# USB_debug_schematic.net
KiCad netlist of a schematic drawn in Altium Designer
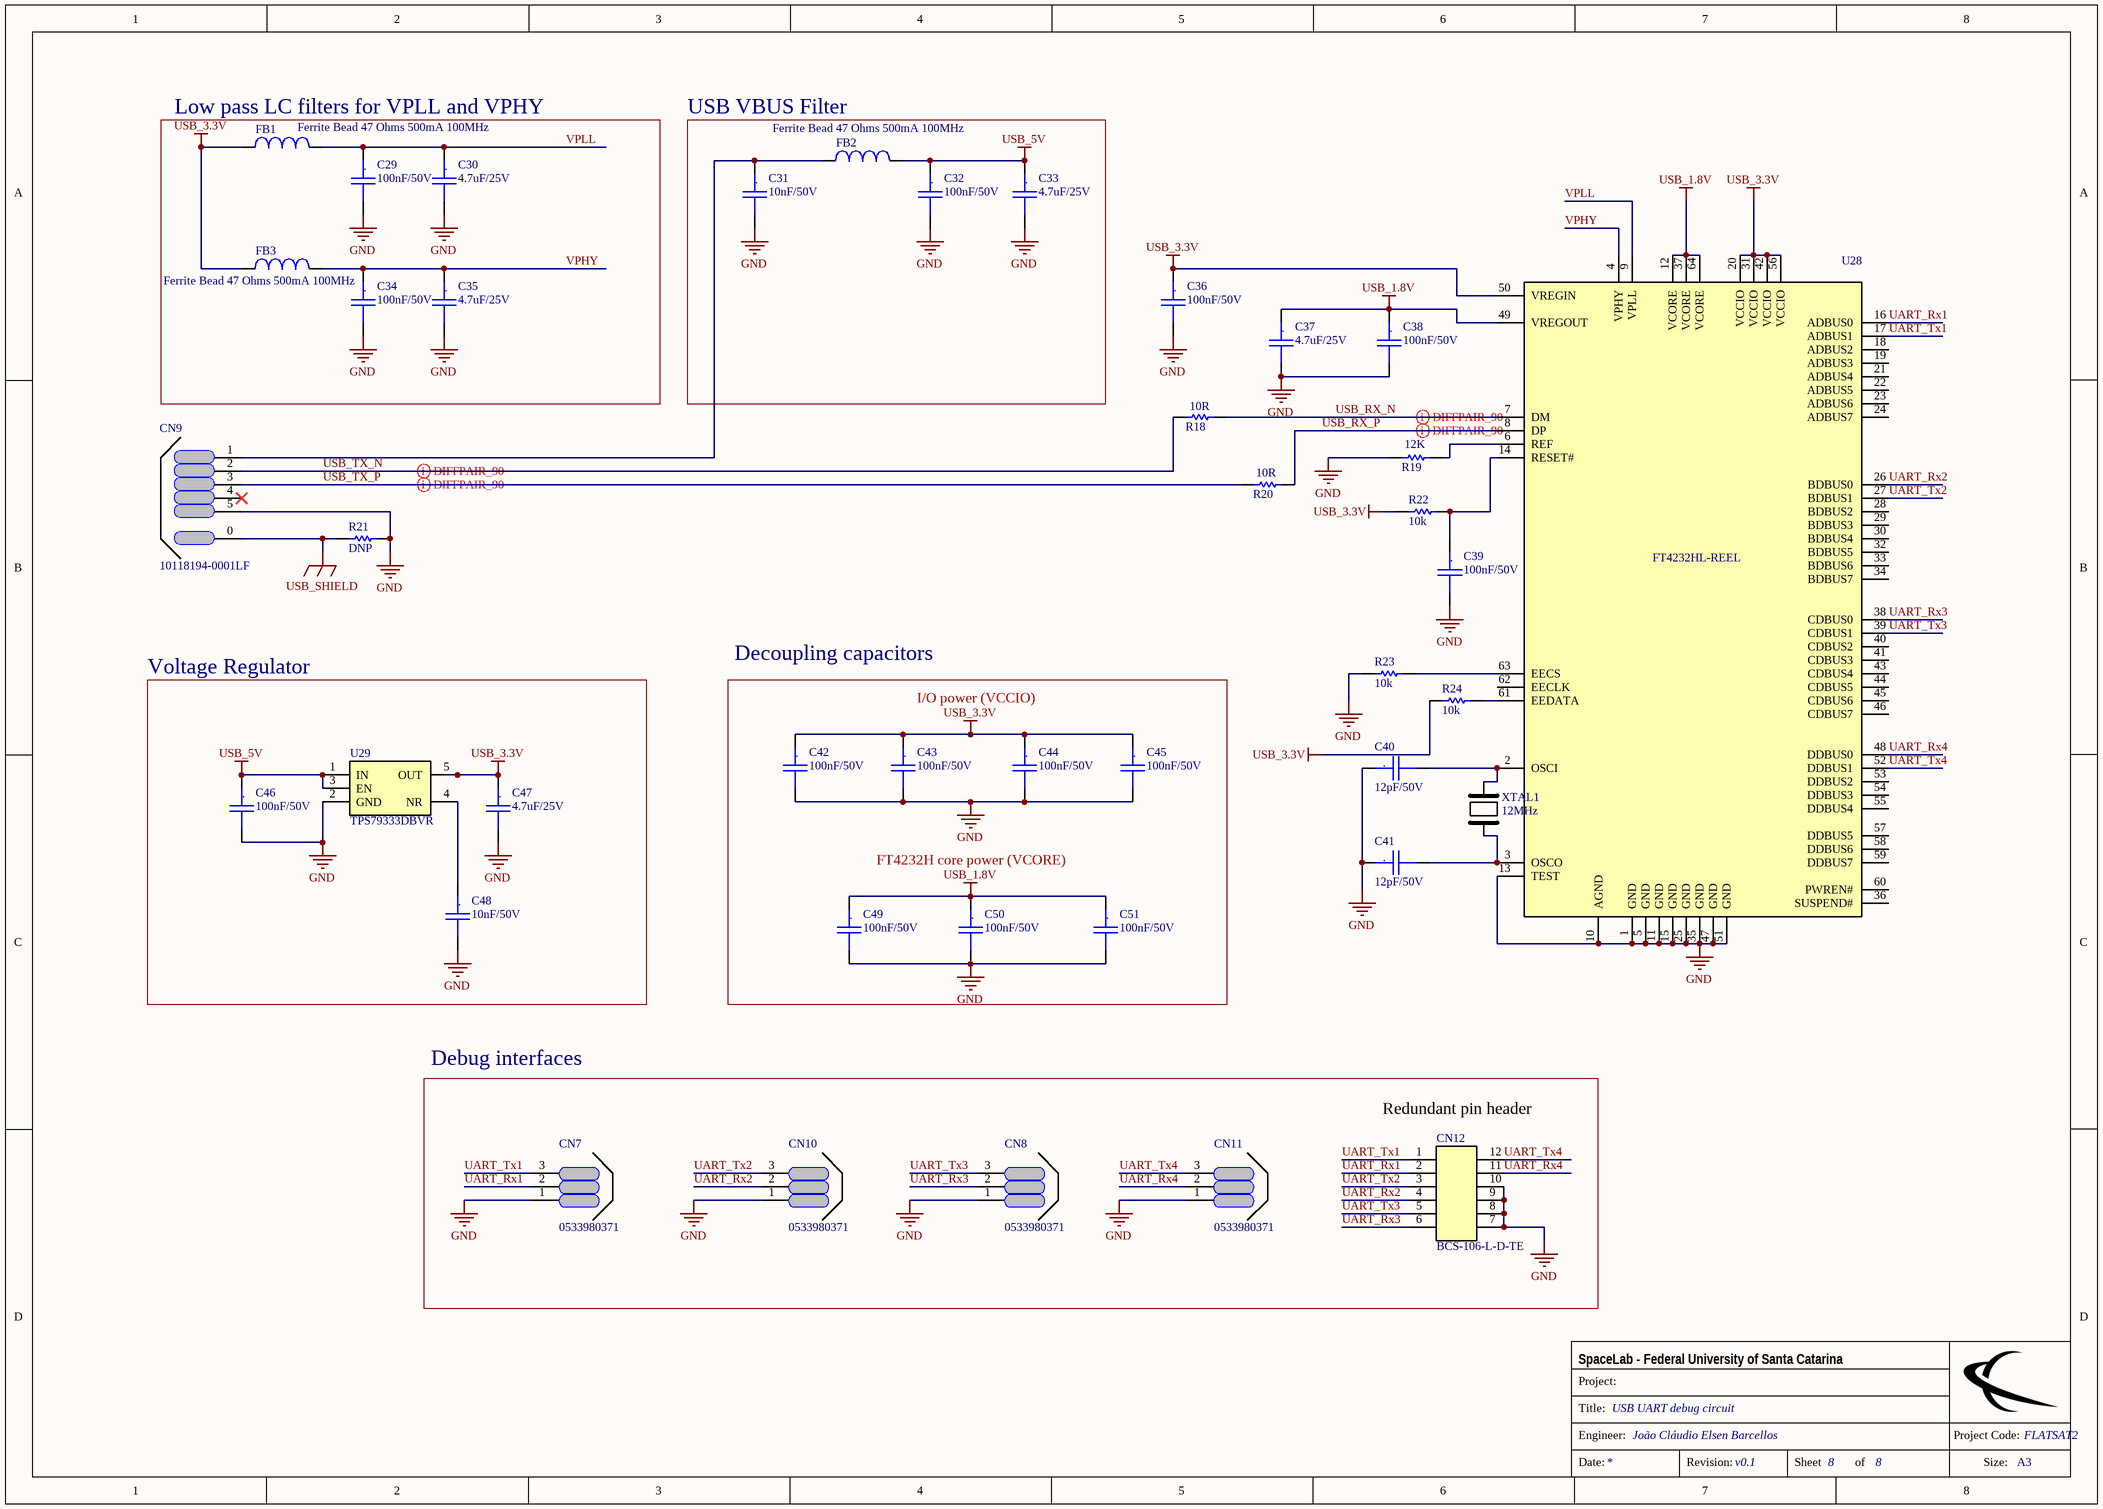
[diagram p0: USB_debug_schematic.SchDoc]

(export (version "E")
  (design (tool "Eeschema 10.0.6"))
  (components
    (comp (ref "C29")
      (value "100nF/50V")
      (footprint "CC0603")
      (description "CAP CER 100nF 50V 10% X7R 0603")
      (fields (field (name "MANUFACTURER PART NUMBER") "C0603C104K5RAC3121"))
      (libsource (lib "flatsat_platform_2") (part "Cap_Cer_X7R_100nF_50V_0603"))
    )
    (comp (ref "C30")
      (value "4.7uF/25V")
      (footprint "CC0805")
      (description "CAP CER 4.7uF 25V 10% X7R 0805")
      (fields (field (name "MANUFACTURER PART NUMBER") "C0805C475K3RACAUTO"))
      (libsource (lib "flatsat_platform_2") (part "Cap_Cer_X7R_4.7uF_25V_0805"))
    )
    (comp (ref "C31")
      (value "10nF/50V")
      (footprint "CC0805")
      (description "CAP CER 0.01uF 50V 10% X7R 0805")
      (fields (field (name "MANUFACTURER PART NUMBER") "08055C103KAT4A"))
      (libsource (lib "flatsat_platform_2") (part "Cap_Cer_X7R_10nF_50V_0805"))
    )
    (comp (ref "C32")
      (value "100nF/50V")
      (footprint "CC0603")
      (description "CAP CER 100nF 50V 10% X7R 0603")
      (fields (field (name "MANUFACTURER PART NUMBER") "C0603C104K5RAC3121"))
      (libsource (lib "flatsat_platform_2") (part "Cap_Cer_X7R_100nF_50V_0603"))
    )
    (comp (ref "C33")
      (value "4.7uF/25V")
      (footprint "CC0805")
      (description "CAP CER 4.7uF 25V 10% X7R 0805")
      (fields (field (name "MANUFACTURER PART NUMBER") "C0805C475K3RACAUTO"))
      (libsource (lib "flatsat_platform_2") (part "Cap_Cer_X7R_4.7uF_25V_0805"))
    )
    (comp (ref "C34")
      (value "100nF/50V")
      (footprint "CC0603")
      (description "CAP CER 100nF 50V 10% X7R 0603")
      (fields (field (name "MANUFACTURER PART NUMBER") "C0603C104K5RAC3121"))
      (libsource (lib "flatsat_platform_2") (part "Cap_Cer_X7R_100nF_50V_0603"))
    )
    (comp (ref "C35")
      (value "4.7uF/25V")
      (footprint "CC0805")
      (description "CAP CER 4.7uF 25V 10% X7R 0805")
      (fields (field (name "MANUFACTURER PART NUMBER") "C0805C475K3RACAUTO"))
      (libsource (lib "flatsat_platform_2") (part "Cap_Cer_X7R_4.7uF_25V_0805"))
    )
    (comp (ref "C36")
      (value "100nF/50V")
      (footprint "CC0603")
      (description "CAP CER 100nF 50V 10% X7R 0603")
      (fields (field (name "MANUFACTURER PART NUMBER") "C0603C104K5RAC3121"))
      (libsource (lib "flatsat_platform_2") (part "Cap_Cer_X7R_100nF_50V_0603"))
    )
    (comp (ref "C37")
      (value "4.7uF/25V")
      (footprint "CC0805")
      (description "CAP CER 4.7uF 25V 10% X7R 0805")
      (fields (field (name "MANUFACTURER PART NUMBER") "C0805C475K3RACAUTO"))
      (libsource (lib "flatsat_platform_2") (part "Cap_Cer_X7R_4.7uF_25V_0805"))
    )
    (comp (ref "C38")
      (value "100nF/50V")
      (footprint "CC0603")
      (description "CAP CER 100nF 50V 10% X7R 0603")
      (fields (field (name "MANUFACTURER PART NUMBER") "C0603C104K5RAC3121"))
      (libsource (lib "flatsat_platform_2") (part "Cap_Cer_X7R_100nF_50V_0603"))
    )
    (comp (ref "C39")
      (value "100nF/50V")
      (footprint "CC0603")
      (description "CAP CER 100nF 50V 10% X7R 0603")
      (fields (field (name "MANUFACTURER PART NUMBER") "C0603C104K5RAC3121"))
      (libsource (lib "flatsat_platform_2") (part "Cap_Cer_X7R_100nF_50V_0603"))
    )
    (comp (ref "C40")
      (value "12pF/50V")
      (footprint "CC0805")
      (description "CAP CER 12pF 50V 1% C0G/NP0 0805")
      (fields (field (name "MANUFACTURER PART NUMBER") "CL21C120FBANNNC"))
      (libsource (lib "flatsat_platform_2") (part "Cap_Cer_X7R_12pF_50V_0805"))
    )
    (comp (ref "C41")
      (value "12pF/50V")
      (footprint "CC0805")
      (description "CAP CER 12pF 50V 1% C0G/NP0 0805")
      (fields (field (name "MANUFACTURER PART NUMBER") "CL21C120FBANNNC"))
      (libsource (lib "flatsat_platform_2") (part "Cap_Cer_X7R_12pF_50V_0805"))
    )
    (comp (ref "C42")
      (value "100nF/50V")
      (footprint "CC0603")
      (description "CAP CER 100nF 50V 10% X7R 0603")
      (fields (field (name "MANUFACTURER PART NUMBER") "C0603C104K5RAC3121"))
      (libsource (lib "flatsat_platform_2") (part "Cap_Cer_X7R_100nF_50V_0603"))
    )
    (comp (ref "C43")
      (value "100nF/50V")
      (footprint "CC0603")
      (description "CAP CER 100nF 50V 10% X7R 0603")
      (fields (field (name "MANUFACTURER PART NUMBER") "C0603C104K5RAC3121"))
      (libsource (lib "flatsat_platform_2") (part "Cap_Cer_X7R_100nF_50V_0603"))
    )
    (comp (ref "C44")
      (value "100nF/50V")
      (footprint "CC0603")
      (description "CAP CER 100nF 50V 10% X7R 0603")
      (fields (field (name "MANUFACTURER PART NUMBER") "C0603C104K5RAC3121"))
      (libsource (lib "flatsat_platform_2") (part "Cap_Cer_X7R_100nF_50V_0603"))
    )
    (comp (ref "C45")
      (value "100nF/50V")
      (footprint "CC0603")
      (description "CAP CER 100nF 50V 10% X7R 0603")
      (fields (field (name "MANUFACTURER PART NUMBER") "C0603C104K5RAC3121"))
      (libsource (lib "flatsat_platform_2") (part "Cap_Cer_X7R_100nF_50V_0603"))
    )
    (comp (ref "C46")
      (value "100nF/50V")
      (footprint "CC0603")
      (description "CAP CER 100nF 50V 10% X7R 0603")
      (fields (field (name "MANUFACTURER PART NUMBER") "C0603C104K5RAC3121"))
      (libsource (lib "flatsat_platform_2") (part "Cap_Cer_X7R_100nF_50V_0603"))
    )
    (comp (ref "C47")
      (value "4.7uF/25V")
      (footprint "CC0805")
      (description "CAP CER 4.7uF 25V 10% X7R 0805")
      (fields (field (name "MANUFACTURER PART NUMBER") "C0805C475K3RACAUTO"))
      (libsource (lib "flatsat_platform_2") (part "Cap_Cer_X7R_4.7uF_25V_0805"))
    )
    (comp (ref "C48")
      (value "10nF/50V")
      (footprint "CC0805")
      (description "CAP CER 0.01uF 50V 10% X7R 0805")
      (fields (field (name "MANUFACTURER PART NUMBER") "08055C103KAT4A"))
      (libsource (lib "flatsat_platform_2") (part "Cap_Cer_X7R_10nF_50V_0805"))
    )
    (comp (ref "C49")
      (value "100nF/50V")
      (footprint "CC0603")
      (description "CAP CER 100nF 50V 10% X7R 0603")
      (fields (field (name "MANUFACTURER PART NUMBER") "C0603C104K5RAC3121"))
      (libsource (lib "flatsat_platform_2") (part "Cap_Cer_X7R_100nF_50V_0603"))
    )
    (comp (ref "C50")
      (value "100nF/50V")
      (footprint "CC0603")
      (description "CAP CER 100nF 50V 10% X7R 0603")
      (fields (field (name "MANUFACTURER PART NUMBER") "C0603C104K5RAC3121"))
      (libsource (lib "flatsat_platform_2") (part "Cap_Cer_X7R_100nF_50V_0603"))
    )
    (comp (ref "C51")
      (value "100nF/50V")
      (footprint "CC0603")
      (description "CAP CER 100nF 50V 10% X7R 0603")
      (fields (field (name "MANUFACTURER PART NUMBER") "C0603C104K5RAC3121"))
      (libsource (lib "flatsat_platform_2") (part "Cap_Cer_X7R_100nF_50V_0603"))
    )
    (comp (ref "CN7")
      (value "0533980371")
      (footprint "PICO BLADE 0533980371")
      (description "CONN HEADER SMD 3POS 1.25MM")
      (fields (field (name "MANUFACTURER") "Molex") (field (name "MANUFACTURER PART NUMBER") "53398-0371"))
      (libsource (lib "flatsat_platform_2") (part "0533980371"))
    )
    (comp (ref "CN8")
      (value "0533980371")
      (footprint "PICO BLADE 0533980371")
      (description "CONN HEADER SMD 3POS 1.25MM")
      (fields (field (name "MANUFACTURER") "Molex") (field (name "MANUFACTURER PART NUMBER") "53398-0371"))
      (libsource (lib "flatsat_platform_2") (part "0533980371"))
    )
    (comp (ref "CN9")
      (value "10118194-0001LF")
      (footprint "MICRO USB B 90GRAUS")
      (description "CONN USB MICRO B RECPT SMT R/A")
      (fields (field (name "MANUFACTURER") "FCI") (field (name "MANUFACTURER PART NUMBER") "10118194-0001LF"))
      (libsource (lib "flatsat_platform_2") (part "10118194-0001LF"))
    )
    (comp (ref "CN10")
      (value "0533980371")
      (footprint "PICO BLADE 0533980371")
      (description "CONN HEADER SMD 3POS 1.25MM")
      (fields (field (name "MANUFACTURER") "Molex") (field (name "MANUFACTURER PART NUMBER") "53398-0371"))
      (libsource (lib "flatsat_platform_2") (part "0533980371"))
    )
    (comp (ref "CN11")
      (value "0533980371")
      (footprint "PICO BLADE 0533980371")
      (description "CONN HEADER SMD 3POS 1.25MM")
      (fields (field (name "MANUFACTURER") "Molex") (field (name "MANUFACTURER PART NUMBER") "53398-0371"))
      (libsource (lib "flatsat_platform_2") (part "0533980371"))
    )
    (comp (ref "CN12")
      (value "BCS-106-L-D-TE")
      (footprint "BCS-106-L-D-TE")
      (description "CONN RCPT 12POS 0.1 GOLD PCB")
      (fields (field (name "MANUFACTURER") "Samtec"))
      (libsource (lib "flatsat_platform_2") (part "BCS-106-L-D-TE"))
    )
    (comp (ref "FB1")
      (value "Ferrite Bead 47 Ohms 500mA 100MHz")
      (footprint "L0603")
      (description "WURTH ELEKTRONIK   742792608   FERRITE BEAD, 47 OHM, 0.5A, 0603")
      (fields (field (name "MANUFACTURER") "Wurth Electronics") (field (name "TOLERANCE") "25%"))
      (libsource (lib "flatsat_platform_2") (part "742792608"))
    )
    (comp (ref "FB2")
      (value "Ferrite Bead 47 Ohms 500mA 100MHz")
      (footprint "L0603")
      (description "WURTH ELEKTRONIK   742792608   FERRITE BEAD, 47 OHM, 0.5A, 0603")
      (fields (field (name "MANUFACTURER") "Wurth Electronics") (field (name "TOLERANCE") "25%"))
      (libsource (lib "flatsat_platform_2") (part "742792608"))
    )
    (comp (ref "FB3")
      (value "Ferrite Bead 47 Ohms 500mA 100MHz")
      (footprint "L0603")
      (description "WURTH ELEKTRONIK   742792608   FERRITE BEAD, 47 OHM, 0.5A, 0603")
      (fields (field (name "MANUFACTURER") "Wurth Electronics") (field (name "TOLERANCE") "25%"))
      (libsource (lib "flatsat_platform_2") (part "742792608"))
    )
    (comp (ref "R18")
      (value "10R")
      (footprint "R0603_MD")
      (description "RES 10R OHM 1/10W 1% 0603")
      (fields (field (name "MANUFACTURER") "Yageo") (field (name "TOLERANCE") "1%"))
      (libsource (lib "flatsat_platform_2") (part "RC0603FR-0710RL"))
    )
    (comp (ref "R19")
      (value "12K")
      (footprint "R0805_MD")
      (description "RES 12K OHM 1/8W 1% 0805")
      (fields
        (field (name "MANUFACTURER") "Stackpole Electronics")
        (field (name "MANUFACTURER PART NUMBER") "RMCF0805FT12K0")
      )
      (libsource (lib "flatsat_platform_2") (part "RMCF0805FT12K0"))
    )
    (comp (ref "R20")
      (value "10R")
      (footprint "R0603_MD")
      (description "RES 10R OHM 1/10W 1% 0603")
      (fields (field (name "MANUFACTURER") "Yageo") (field (name "TOLERANCE") "1%"))
      (libsource (lib "flatsat_platform_2") (part "RC0603FR-0710RL"))
    )
    (comp (ref "R21")
      (value "DNP")
      (footprint "0805")
      (description "RES DNP 0805")
      (fields (field (name "MANUFACTURER PART NUMBER") "CRCW08050000Z0EA"))
      (libsource (lib "flatsat_platform_2") (part "RDNP_0805"))
    )
    (comp (ref "R22")
      (value "10k")
      (footprint "0805")
      (description "RES 10K OHM 1/8W 1%  0805")
      (fields (field (name "MANUFACTURER PART NUMBER") "CRCW080510K0FKEA"))
      (libsource (lib "flatsat_platform_2") (part "R10k_1%_1/8W_0805"))
    )
    (comp (ref "R23")
      (value "10k")
      (footprint "0805")
      (description "RES 10K OHM 1/8W 1%  0805")
      (fields (field (name "MANUFACTURER PART NUMBER") "CRCW080510K0FKEA"))
      (libsource (lib "flatsat_platform_2") (part "R10k_1%_1/8W_0805"))
    )
    (comp (ref "R24")
      (value "10k")
      (footprint "0805")
      (description "RES 10K OHM 1/8W 1%  0805")
      (fields (field (name "MANUFACTURER PART NUMBER") "CRCW080510K0FKEA"))
      (libsource (lib "flatsat_platform_2") (part "R10k_1%_1/8W_0805"))
    )
    (comp (ref "U28")
      (value "FT4232HL-REEL")
      (footprint "LQFP-64")
      (description "FTDI - FT4232HL-REEL - USB-UART/MPSSE, 4232, QUAD, 64LQFP")
      (fields (field (name "MANUFACTURER") "FTDI"))
      (libsource (lib "flatsat_platform_2") (part "FT4232HL-REEL"))
    )
    (comp (ref "U29")
      (value "TPS79333DBVR")
      (footprint "SOT23-5")
      (description "TEXAS INSTRUMENTS - TPS79333DBVR - IC, V REG, LINEAR, 0.2A, SOT-23-5")
      (fields (field (name "MANUFACTURER") "Texas Instruments"))
      (libsource (lib "flatsat_platform_2") (part "TPS79333DBVR"))
    )
    (comp (ref "XTAL1")
      (value "12.000MHz 12pF")
      (footprint "TXC 7A Series")
      (description "Crystals 12.000MHz 30ppm 12pF -40C to 85C")
      (fields
        (field (name "MANUFACTURER") "TXC")
        (field (name "TOLERANCE") "30ppm")
        (field (name "FREQUENCY") "12MHz")
      )
      (libsource (lib "flatsat_platform_2") (part "AA-12.000MAGE-T"))
    )
  )
  (nets
    (net (code "1") (name "/UART_Rx1") (class "Default")
      (node (ref "CN12") (pin "2") (pintype "passive"))
      (node (ref "CN7") (pin "2") (pinfunction "2_2") (pintype "passive"))
      (node (ref "U28") (pin "16") (pinfunction "ADBUS0_16") (pintype "power_in"))
    )
    (net (code "2") (name "/UART_Rx2") (class "Default")
      (node (ref "CN10") (pin "2") (pinfunction "2_2") (pintype "passive"))
      (node (ref "CN12") (pin "4") (pintype "passive"))
      (node (ref "U28") (pin "26") (pinfunction "BDBUS0_26") (pintype "power_in"))
    )
    (net (code "3") (name "/UART_Rx3") (class "Default")
      (node (ref "CN12") (pin "6") (pintype "passive"))
      (node (ref "CN8") (pin "2") (pinfunction "2_2") (pintype "passive"))
      (node (ref "U28") (pin "38") (pinfunction "CDBUS0_38") (pintype "power_in"))
    )
    (net (code "4") (name "/UART_Rx4") (class "Default")
      (node (ref "CN11") (pin "2") (pinfunction "2_2") (pintype "passive"))
      (node (ref "CN12") (pin "11") (pintype "passive"))
      (node (ref "U28") (pin "48") (pinfunction "DDBUS0_48") (pintype "power_in"))
    )
    (net (code "5") (name "/UART_Tx1") (class "Default")
      (node (ref "CN12") (pin "1") (pintype "passive"))
      (node (ref "CN7") (pin "3") (pinfunction "3_3") (pintype "passive"))
      (node (ref "U28") (pin "17") (pinfunction "ADBUS1_17") (pintype "power_in"))
    )
    (net (code "6") (name "/UART_Tx2") (class "Default")
      (node (ref "CN10") (pin "3") (pinfunction "3_3") (pintype "passive"))
      (node (ref "CN12") (pin "3") (pintype "passive"))
      (node (ref "U28") (pin "27") (pinfunction "BDBUS1_27") (pintype "power_in"))
    )
    (net (code "7") (name "/UART_Tx3") (class "Default")
      (node (ref "CN12") (pin "5") (pintype "passive"))
      (node (ref "CN8") (pin "3") (pinfunction "3_3") (pintype "passive"))
      (node (ref "U28") (pin "39") (pinfunction "CDBUS1_39") (pintype "power_in"))
    )
    (net (code "8") (name "/UART_Tx4") (class "Default")
      (node (ref "CN11") (pin "3") (pinfunction "3_3") (pintype "passive"))
      (node (ref "CN12") (pin "12") (pintype "passive"))
      (node (ref "U28") (pin "52") (pinfunction "DDBUS1_52") (pintype "power_in"))
    )
    (net (code "9") (name "/USB_RX_N") (class "Default")
      (node (ref "R18") (pin "2") (pinfunction "2_2") (pintype "passive"))
      (node (ref "U28") (pin "7") (pinfunction "DM_7") (pintype "power_in"))
    )
    (net (code "10") (name "/USB_RX_P") (class "Default")
      (node (ref "R20") (pin "2") (pinfunction "2_2") (pintype "passive"))
      (node (ref "U28") (pin "8") (pinfunction "DP_8") (pintype "power_in"))
    )
    (net (code "11") (name "/USB_TX_N") (class "Default")
      (node (ref "CN9") (pin "2") (pinfunction "2_2") (pintype "passive"))
      (node (ref "R18") (pin "1") (pinfunction "1_1") (pintype "passive"))
    )
    (net (code "12") (name "/USB_TX_P") (class "Default")
      (node (ref "CN9") (pin "3") (pinfunction "3_3") (pintype "passive"))
      (node (ref "R20") (pin "1") (pinfunction "1_1") (pintype "passive"))
    )
    (net (code "13") (name "/VPHY") (class "Default")
      (node (ref "C34") (pin "1") (pinfunction "1_1") (pintype "passive"))
      (node (ref "C35") (pin "1") (pinfunction "1_1") (pintype "passive"))
      (node (ref "FB3") (pin "2") (pinfunction "2_2") (pintype "passive"))
      (node (ref "U28") (pin "4") (pinfunction "VPHY_4") (pintype "power_in"))
    )
    (net (code "14") (name "/VPLL") (class "Default")
      (node (ref "C29") (pin "1") (pinfunction "1_1") (pintype "passive"))
      (node (ref "C30") (pin "1") (pinfunction "1_1") (pintype "passive"))
      (node (ref "FB1") (pin "2") (pinfunction "2_2") (pintype "passive"))
      (node (ref "U28") (pin "9") (pinfunction "VPLL_9") (pintype "power_in"))
    )
    (net (code "15") (name "GND") (class "Default")
      (node (ref "C29") (pin "2") (pinfunction "2_2") (pintype "passive"))
      (node (ref "C30") (pin "2") (pinfunction "2_2") (pintype "passive"))
      (node (ref "C31") (pin "2") (pinfunction "2_2") (pintype "passive"))
      (node (ref "C32") (pin "2") (pinfunction "2_2") (pintype "passive"))
      (node (ref "C33") (pin "2") (pinfunction "2_2") (pintype "passive"))
      (node (ref "C34") (pin "2") (pinfunction "2_2") (pintype "passive"))
      (node (ref "C35") (pin "2") (pinfunction "2_2") (pintype "passive"))
      (node (ref "C36") (pin "2") (pinfunction "2_2") (pintype "passive"))
      (node (ref "C37") (pin "2") (pinfunction "2_2") (pintype "passive"))
      (node (ref "C38") (pin "2") (pinfunction "2_2") (pintype "passive"))
      (node (ref "C39") (pin "2") (pinfunction "2_2") (pintype "passive"))
      (node (ref "C40") (pin "1") (pinfunction "1_1") (pintype "passive"))
      (node (ref "C41") (pin "1") (pinfunction "1_1") (pintype "passive"))
      (node (ref "C42") (pin "2") (pinfunction "2_2") (pintype "passive"))
      (node (ref "C43") (pin "2") (pinfunction "2_2") (pintype "passive"))
      (node (ref "C44") (pin "2") (pinfunction "2_2") (pintype "passive"))
      (node (ref "C45") (pin "2") (pinfunction "2_2") (pintype "passive"))
      (node (ref "C46") (pin "2") (pinfunction "2_2") (pintype "passive"))
      (node (ref "C47") (pin "2") (pinfunction "2_2") (pintype "passive"))
      (node (ref "C48") (pin "2") (pinfunction "2_2") (pintype "passive"))
      (node (ref "C49") (pin "2") (pinfunction "2_2") (pintype "passive"))
      (node (ref "C50") (pin "2") (pinfunction "2_2") (pintype "passive"))
      (node (ref "C51") (pin "2") (pinfunction "2_2") (pintype "passive"))
      (node (ref "CN10") (pin "1") (pinfunction "1_1") (pintype "passive"))
      (node (ref "CN11") (pin "1") (pinfunction "1_1") (pintype "passive"))
      (node (ref "CN12") (pin "10") (pintype "passive"))
      (node (ref "CN12") (pin "7") (pintype "passive"))
      (node (ref "CN12") (pin "8") (pintype "passive"))
      (node (ref "CN12") (pin "9") (pintype "passive"))
      (node (ref "CN7") (pin "1") (pinfunction "1_1") (pintype "passive"))
      (node (ref "CN8") (pin "1") (pinfunction "1_1") (pintype "passive"))
      (node (ref "CN9") (pin "5") (pinfunction "5_5") (pintype "passive"))
      (node (ref "R19") (pin "1") (pinfunction "1_1") (pintype "passive"))
      (node (ref "R21") (pin "1") (pinfunction "1_1") (pintype "passive"))
      (node (ref "R23") (pin "2") (pinfunction "2_2") (pintype "passive"))
      (node (ref "U28") (pin "1") (pinfunction "GND_1") (pintype "passive"))
      (node (ref "U28") (pin "10") (pinfunction "AGND_10") (pintype "passive"))
      (node (ref "U28") (pin "11") (pinfunction "GND_11") (pintype "passive"))
      (node (ref "U28") (pin "13") (pinfunction "TEST_13") (pintype "power_in"))
      (node (ref "U28") (pin "15") (pinfunction "GND_15") (pintype "passive"))
      (node (ref "U28") (pin "25") (pinfunction "GND_25") (pintype "passive"))
      (node (ref "U28") (pin "35") (pinfunction "GND_35") (pintype "passive"))
      (node (ref "U28") (pin "47") (pinfunction "GND_47") (pintype "passive"))
      (node (ref "U28") (pin "5") (pinfunction "GND_5") (pintype "passive"))
      (node (ref "U28") (pin "51") (pinfunction "GND_51") (pintype "passive"))
      (node (ref "U29") (pin "2") (pinfunction "GND_2") (pintype "passive"))
    )
    (net (code "16") (name "Net-(C31-Pad1)") (class "Default")
      (node (ref "C31") (pin "1") (pinfunction "1_1") (pintype "passive"))
      (node (ref "CN9") (pin "1") (pinfunction "1_1") (pintype "passive"))
      (node (ref "FB2") (pin "1") (pinfunction "1_1") (pintype "passive"))
    )
    (net (code "17") (name "Net-(U28-EECS)") (class "Default")
      (node (ref "R23") (pin "1") (pinfunction "1_1") (pintype "passive"))
      (node (ref "U28") (pin "63") (pinfunction "EECS_63") (pintype "power_in"))
    )
    (net (code "18") (name "Net-(U28-EEDATA)") (class "Default")
      (node (ref "R24") (pin "1") (pinfunction "1_1") (pintype "passive"))
      (node (ref "U28") (pin "61") (pinfunction "EEDATA_61") (pintype "power_in"))
    )
    (net (code "19") (name "Net-(U28-OSCI)") (class "Default")
      (node (ref "C40") (pin "2") (pinfunction "2_2") (pintype "passive"))
      (node (ref "U28") (pin "2") (pinfunction "OSCI_2") (pintype "power_in"))
      (node (ref "XTAL1") (pin "1") (pinfunction "1_1") (pintype "passive"))
    )
    (net (code "20") (name "Net-(U28-OSCO)") (class "Default")
      (node (ref "C41") (pin "2") (pinfunction "2_2") (pintype "passive"))
      (node (ref "U28") (pin "3") (pinfunction "OSCO_3") (pintype "power_in"))
      (node (ref "XTAL1") (pin "2") (pinfunction "2_2") (pintype "passive"))
    )
    (net (code "21") (name "Net-(U28-REF)") (class "Default")
      (node (ref "R19") (pin "2") (pinfunction "2_2") (pintype "passive"))
      (node (ref "U28") (pin "6") (pinfunction "REF_6") (pintype "power_in"))
    )
    (net (code "22") (name "Net-(U28-RESET#)") (class "Default")
      (node (ref "C39") (pin "1") (pinfunction "1_1") (pintype "passive"))
      (node (ref "R22") (pin "1") (pinfunction "1_1") (pintype "passive"))
      (node (ref "U28") (pin "14") (pinfunction "RESET#_14") (pintype "power_in"))
    )
    (net (code "23") (name "Net-(U29-NR)") (class "Default")
      (node (ref "C48") (pin "1") (pinfunction "1_1") (pintype "passive"))
      (node (ref "U29") (pin "4") (pinfunction "NR_4") (pintype "passive"))
    )
    (net (code "24") (name "USB_1.8V") (class "Default")
      (node (ref "C37") (pin "1") (pinfunction "1_1") (pintype "passive"))
      (node (ref "C38") (pin "1") (pinfunction "1_1") (pintype "passive"))
      (node (ref "C49") (pin "1") (pinfunction "1_1") (pintype "passive"))
      (node (ref "C50") (pin "1") (pinfunction "1_1") (pintype "passive"))
      (node (ref "C51") (pin "1") (pinfunction "1_1") (pintype "passive"))
      (node (ref "U28") (pin "12") (pinfunction "VCORE_12") (pintype "power_in"))
      (node (ref "U28") (pin "37") (pinfunction "VCORE_37") (pintype "power_in"))
      (node (ref "U28") (pin "49") (pinfunction "VREGOUT_49") (pintype "power_in"))
      (node (ref "U28") (pin "64") (pinfunction "VCORE_64") (pintype "power_in"))
    )
    (net (code "25") (name "USB_3.3V") (class "Default")
      (node (ref "C36") (pin "1") (pinfunction "1_1") (pintype "passive"))
      (node (ref "C42") (pin "1") (pinfunction "1_1") (pintype "passive"))
      (node (ref "C43") (pin "1") (pinfunction "1_1") (pintype "passive"))
      (node (ref "C44") (pin "1") (pinfunction "1_1") (pintype "passive"))
      (node (ref "C45") (pin "1") (pinfunction "1_1") (pintype "passive"))
      (node (ref "C47") (pin "1") (pinfunction "1_1") (pintype "passive"))
      (node (ref "FB1") (pin "1") (pinfunction "1_1") (pintype "passive"))
      (node (ref "FB3") (pin "1") (pinfunction "1_1") (pintype "passive"))
      (node (ref "R22") (pin "2") (pinfunction "2_2") (pintype "passive"))
      (node (ref "R24") (pin "2") (pinfunction "2_2") (pintype "passive"))
      (node (ref "U28") (pin "20") (pinfunction "VCCIO_20") (pintype "power_in"))
      (node (ref "U28") (pin "31") (pinfunction "VCCIO_31") (pintype "power_in"))
      (node (ref "U28") (pin "42") (pinfunction "VCCIO_42") (pintype "power_in"))
      (node (ref "U28") (pin "50") (pinfunction "VREGIN_50") (pintype "power_in"))
      (node (ref "U28") (pin "56") (pinfunction "VCCIO_56") (pintype "power_in"))
      (node (ref "U29") (pin "5") (pinfunction "OUT_5") (pintype "passive"))
    )
    (net (code "26") (name "USB_5V") (class "Default")
      (node (ref "C32") (pin "1") (pinfunction "1_1") (pintype "passive"))
      (node (ref "C33") (pin "1") (pinfunction "1_1") (pintype "passive"))
      (node (ref "C46") (pin "1") (pinfunction "1_1") (pintype "passive"))
      (node (ref "FB2") (pin "2") (pinfunction "2_2") (pintype "passive"))
      (node (ref "U29") (pin "1") (pinfunction "IN_1") (pintype "passive"))
      (node (ref "U29") (pin "3") (pinfunction "EN_3") (pintype "passive"))
    )
    (net (code "27") (name "USB_SHIELD") (class "Default")
      (node (ref "CN9") (pin "0") (pinfunction "0_0") (pintype "passive"))
      (node (ref "R21") (pin "2") (pinfunction "2_2") (pintype "passive"))
    )
    (net (code "28") (name "unconnected-(CN9-Pad4)") (class "Default")
      (node (ref "CN9") (pin "4") (pinfunction "4_4") (pintype "passive+no_connect"))
    )
    (net (code "29") (name "unconnected-(U28-ADBUS2-Pad18)") (class "Default")
      (node (ref "U28") (pin "18") (pinfunction "ADBUS2_18") (pintype "power_in"))
    )
    (net (code "30") (name "unconnected-(U28-ADBUS3-Pad19)") (class "Default")
      (node (ref "U28") (pin "19") (pinfunction "ADBUS3_19") (pintype "power_in"))
    )
    (net (code "31") (name "unconnected-(U28-ADBUS4-Pad21)") (class "Default")
      (node (ref "U28") (pin "21") (pinfunction "ADBUS4_21") (pintype "power_in"))
    )
    (net (code "32") (name "unconnected-(U28-ADBUS5-Pad22)") (class "Default")
      (node (ref "U28") (pin "22") (pinfunction "ADBUS5_22") (pintype "power_in"))
    )
    (net (code "33") (name "unconnected-(U28-ADBUS6-Pad23)") (class "Default")
      (node (ref "U28") (pin "23") (pinfunction "ADBUS6_23") (pintype "power_in"))
    )
    (net (code "34") (name "unconnected-(U28-ADBUS7-Pad24)") (class "Default")
      (node (ref "U28") (pin "24") (pinfunction "ADBUS7_24") (pintype "power_in"))
    )
    (net (code "35") (name "unconnected-(U28-BDBUS2-Pad28)") (class "Default")
      (node (ref "U28") (pin "28") (pinfunction "BDBUS2_28") (pintype "power_in"))
    )
    (net (code "36") (name "unconnected-(U28-BDBUS3-Pad29)") (class "Default")
      (node (ref "U28") (pin "29") (pinfunction "BDBUS3_29") (pintype "power_in"))
    )
    (net (code "37") (name "unconnected-(U28-BDBUS4-Pad30)") (class "Default")
      (node (ref "U28") (pin "30") (pinfunction "BDBUS4_30") (pintype "power_in"))
    )
    (net (code "38") (name "unconnected-(U28-BDBUS5-Pad32)") (class "Default")
      (node (ref "U28") (pin "32") (pinfunction "BDBUS5_32") (pintype "power_in"))
    )
    (net (code "39") (name "unconnected-(U28-BDBUS6-Pad33)") (class "Default")
      (node (ref "U28") (pin "33") (pinfunction "BDBUS6_33") (pintype "power_in"))
    )
    (net (code "40") (name "unconnected-(U28-BDBUS7-Pad34)") (class "Default")
      (node (ref "U28") (pin "34") (pinfunction "BDBUS7_34") (pintype "power_in"))
    )
    (net (code "41") (name "unconnected-(U28-CDBUS2-Pad40)") (class "Default")
      (node (ref "U28") (pin "40") (pinfunction "CDBUS2_40") (pintype "power_in"))
    )
    (net (code "42") (name "unconnected-(U28-CDBUS3-Pad41)") (class "Default")
      (node (ref "U28") (pin "41") (pinfunction "CDBUS3_41") (pintype "power_in"))
    )
    (net (code "43") (name "unconnected-(U28-CDBUS4-Pad43)") (class "Default")
      (node (ref "U28") (pin "43") (pinfunction "CDBUS4_43") (pintype "power_in"))
    )
    (net (code "44") (name "unconnected-(U28-CDBUS5-Pad44)") (class "Default")
      (node (ref "U28") (pin "44") (pinfunction "CDBUS5_44") (pintype "power_in"))
    )
    (net (code "45") (name "unconnected-(U28-CDBUS6-Pad45)") (class "Default")
      (node (ref "U28") (pin "45") (pinfunction "CDBUS6_45") (pintype "power_in"))
    )
    (net (code "46") (name "unconnected-(U28-CDBUS7-Pad46)") (class "Default")
      (node (ref "U28") (pin "46") (pinfunction "CDBUS7_46") (pintype "power_in"))
    )
    (net (code "47") (name "unconnected-(U28-DDBUS2-Pad53)") (class "Default")
      (node (ref "U28") (pin "53") (pinfunction "DDBUS2_53") (pintype "power_in"))
    )
    (net (code "48") (name "unconnected-(U28-DDBUS3-Pad54)") (class "Default")
      (node (ref "U28") (pin "54") (pinfunction "DDBUS3_54") (pintype "power_in"))
    )
    (net (code "49") (name "unconnected-(U28-DDBUS4-Pad55)") (class "Default")
      (node (ref "U28") (pin "55") (pinfunction "DDBUS4_55") (pintype "power_in"))
    )
    (net (code "50") (name "unconnected-(U28-DDBUS5-Pad57)") (class "Default")
      (node (ref "U28") (pin "57") (pinfunction "DDBUS5_57") (pintype "power_in"))
    )
    (net (code "51") (name "unconnected-(U28-DDBUS6-Pad58)") (class "Default")
      (node (ref "U28") (pin "58") (pinfunction "DDBUS6_58") (pintype "power_in"))
    )
    (net (code "52") (name "unconnected-(U28-DDBUS7-Pad59)") (class "Default")
      (node (ref "U28") (pin "59") (pinfunction "DDBUS7_59") (pintype "power_in"))
    )
    (net (code "53") (name "unconnected-(U28-EECLK-Pad62)") (class "Default")
      (node (ref "U28") (pin "62") (pinfunction "EECLK_62") (pintype "power_in"))
    )
    (net (code "54") (name "unconnected-(U28-PWREN#-Pad60)") (class "Default")
      (node (ref "U28") (pin "60") (pinfunction "PWREN#_60") (pintype "power_in"))
    )
    (net (code "55") (name "unconnected-(U28-SUSPEND#-Pad36)") (class "Default")
      (node (ref "U28") (pin "36") (pinfunction "SUSPEND#_36") (pintype "power_in"))
    )
  )
)
